# Nucleo_Shield.net
KiCad netlist of a schematic drawn in Altium Designer
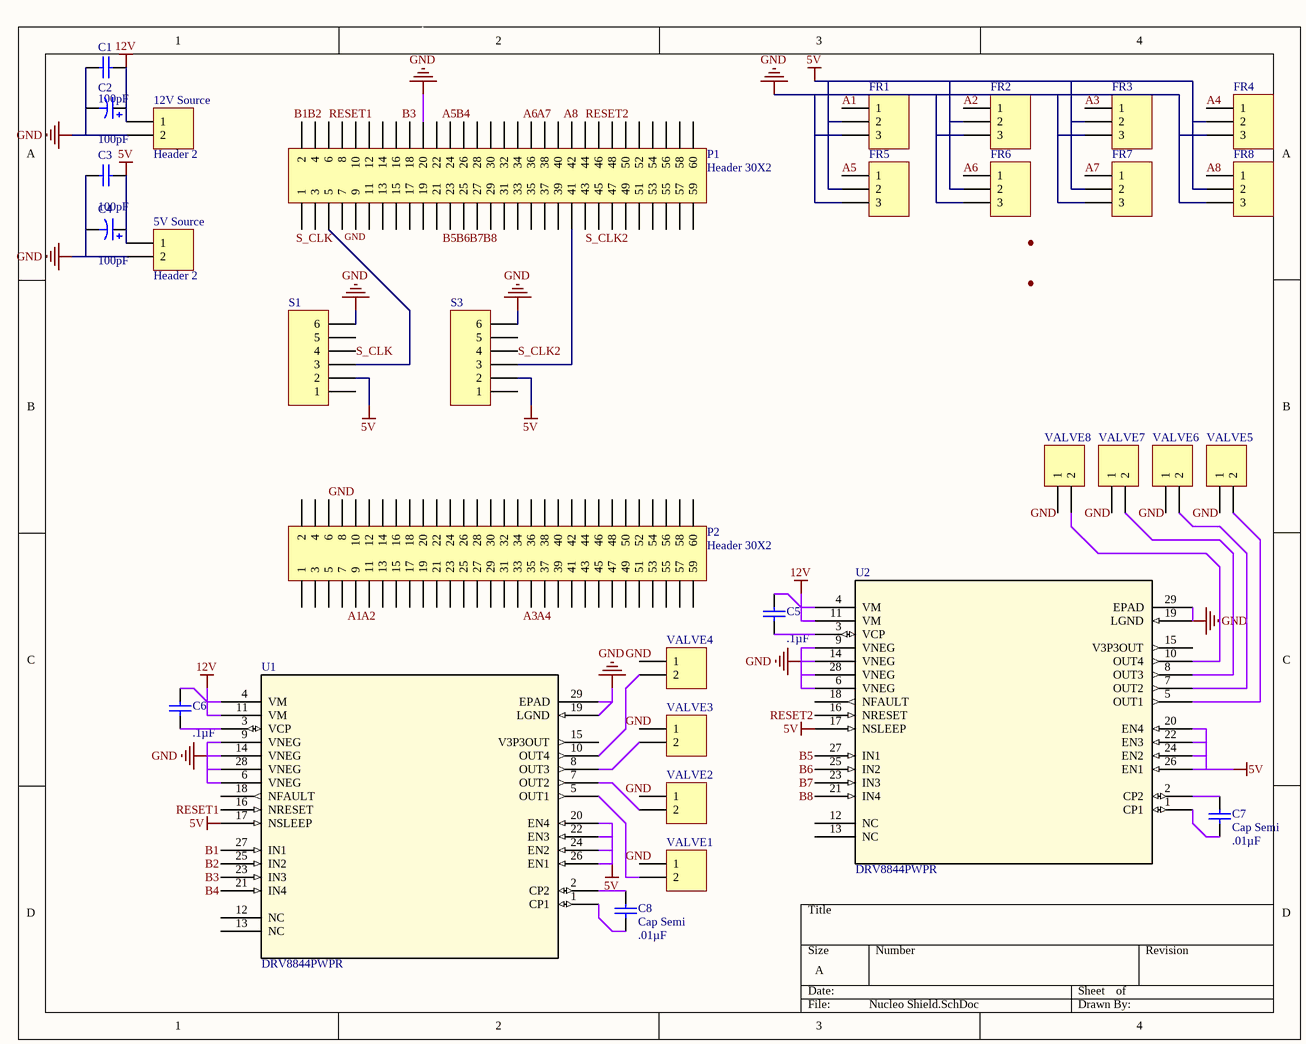
[diagram p0: Nucleo Shield.SchDoc]

(export (version "E")
  (design (tool "Eeschema 10.0.6"))
  (components
    (comp (ref "5V Source")
      (value "Header 2")
      (footprint "HDR1X2")
      (description "Header, 2-Pin")
      (fields (field (name "PUBLISHER") "Altium Limited"))
      (libsource (lib "Miscellaneous Connectors") (part "Header 2"))
    )
    (comp (ref "12V Source")
      (value "Header 2")
      (footprint "HDR1X2")
      (description "Header, 2-Pin")
      (fields (field (name "PUBLISHER") "Altium Limited"))
      (libsource (lib "Miscellaneous Connectors") (part "Header 2"))
    )
    (comp (ref "C1")
      (value "100pF")
      (footprint "C1206")
      (description "Capacitor (Semiconductor SIM Model)")
      (fields (field (name "Comment") "Cap Semi") (field (name "PUBLISHER") "Altium Limited"))
      (libsource (lib "Miscellaneous Devices") (part "Cap Semi"))
    )
    (comp (ref "C2")
      (value "100pF")
      (footprint "C0805")
      (description "Polarized Capacitor (Surface Mount)")
      (fields (field (name "Comment") "Cap Pol3") (field (name "PUBLISHER") "Altium Limited"))
      (libsource (lib "Miscellaneous Devices") (part "Cap Pol3"))
    )
    (comp (ref "C3")
      (value "100pF")
      (footprint "C1206")
      (description "Capacitor (Semiconductor SIM Model)")
      (fields (field (name "Comment") "Cap Semi") (field (name "PUBLISHER") "Altium Limited"))
      (libsource (lib "Miscellaneous Devices") (part "Cap Semi"))
    )
    (comp (ref "C4")
      (value "100pF")
      (footprint "C0805")
      (description "Polarized Capacitor (Surface Mount)")
      (fields (field (name "Comment") "Cap Pol3") (field (name "PUBLISHER") "Altium Limited"))
      (libsource (lib "Miscellaneous Devices") (part "Cap Pol3"))
    )
    (comp (ref "C5")
      (value ".1µF")
      (footprint "C1206")
      (description "Capacitor (Semiconductor SIM Model)")
      (fields (field (name "Comment") "Cap Semi") (field (name "PUBLISHER") "Altium Limited"))
      (libsource (lib "Miscellaneous Devices") (part "Cap Semi"))
    )
    (comp (ref "C6")
      (value ".1µF")
      (footprint "C1206")
      (description "Capacitor (Semiconductor SIM Model)")
      (fields (field (name "Comment") "Cap Semi") (field (name "PUBLISHER") "Altium Limited"))
      (libsource (lib "Miscellaneous Devices") (part "Cap Semi"))
    )
    (comp (ref "C7")
      (value "Cap Semi")
      (footprint "C1206")
      (description "Capacitor (Semiconductor SIM Model)")
      (fields (field (name "ALTIUM_VALUE") ".01µF") (field (name "PUBLISHER") "Altium Limited"))
      (libsource (lib "Miscellaneous Devices") (part "Cap Semi"))
    )
    (comp (ref "C8")
      (value "Cap Semi")
      (footprint "C1206")
      (description "Capacitor (Semiconductor SIM Model)")
      (fields (field (name "ALTIUM_VALUE") ".01µF") (field (name "PUBLISHER") "Altium Limited"))
      (libsource (lib "Miscellaneous Devices") (part "Cap Semi"))
    )
    (comp (ref "FR1")
      (value "FlowRate Sense")
      (footprint "HDR1X3")
      (description "Header, 3-Pin")
      (fields (field (name "PUBLISHER") "Altium Limited"))
      (libsource (lib "Miscellaneous Connectors") (part "Header 3"))
    )
    (comp (ref "FR2")
      (value "FlowRate Sense")
      (footprint "HDR1X3")
      (description "Header, 3-Pin")
      (fields (field (name "PUBLISHER") "Altium Limited"))
      (libsource (lib "Miscellaneous Connectors") (part "Header 3"))
    )
    (comp (ref "FR3")
      (value "FlowRate Sense")
      (footprint "HDR1X3")
      (description "Header, 3-Pin")
      (fields (field (name "PUBLISHER") "Altium Limited"))
      (libsource (lib "Miscellaneous Connectors") (part "Header 3"))
    )
    (comp (ref "FR4")
      (value "FlowRate Sense")
      (footprint "HDR1X3")
      (description "Header, 3-Pin")
      (fields (field (name "PUBLISHER") "Altium Limited"))
      (libsource (lib "Miscellaneous Connectors") (part "Header 3"))
    )
    (comp (ref "FR5")
      (value "FlowRate Sense")
      (footprint "HDR1X3")
      (description "Header, 3-Pin")
      (fields (field (name "PUBLISHER") "Altium Limited"))
      (libsource (lib "Miscellaneous Connectors") (part "Header 3"))
    )
    (comp (ref "FR6")
      (value "FlowRate Sense")
      (footprint "HDR1X3")
      (description "Header, 3-Pin")
      (fields (field (name "PUBLISHER") "Altium Limited"))
      (libsource (lib "Miscellaneous Connectors") (part "Header 3"))
    )
    (comp (ref "FR7")
      (value "FlowRate Sense")
      (footprint "HDR1X3")
      (description "Header, 3-Pin")
      (fields (field (name "PUBLISHER") "Altium Limited"))
      (libsource (lib "Miscellaneous Connectors") (part "Header 3"))
    )
    (comp (ref "FR8")
      (value "FlowRate Sense")
      (footprint "HDR1X3")
      (description "Header, 3-Pin")
      (fields (field (name "PUBLISHER") "Altium Limited"))
      (libsource (lib "Miscellaneous Connectors") (part "Header 3"))
    )
    (comp (ref "P1")
      (value "Header 30X2")
      (footprint "HDR2X30")
      (description "Header, 30-Pin, Dual row")
      (fields (field (name "PUBLISHER") "Altium Limited"))
      (libsource (lib "Miscellaneous Connectors") (part "Header 30X2"))
    )
    (comp (ref "P2")
      (value "Header 30X2")
      (footprint "HDR2X30")
      (description "Header, 30-Pin, Dual row")
      (fields (field (name "PUBLISHER") "Altium Limited"))
      (libsource (lib "Miscellaneous Connectors") (part "Header 30X2"))
    )
    (comp (ref "S1")
      (value "Header 6")
      (footprint "HDR1X6")
      (description "Header, 6-Pin")
      (fields (field (name "PUBLISHER") "Altium Limited"))
      (libsource (lib "Miscellaneous Connectors") (part "Header 6"))
    )
    (comp (ref "S3")
      (value "Header 6")
      (footprint "HDR1X6")
      (description "Header, 6-Pin")
      (fields (field (name "PUBLISHER") "Altium Limited"))
      (libsource (lib "Miscellaneous Connectors") (part "Header 6"))
    )
    (comp (ref "U1")
      (value "DRV8844PWPR")
      (footprint "PWP28_5P18X3P1")
      (description "Imported")
      (libsource (lib "AltiumDesigner") (part "DRV8844PWPR"))
    )
    (comp (ref "U2")
      (value "DRV8844PWPR")
      (footprint "PWP28_5P18X3P1")
      (description "Imported")
      (libsource (lib "AltiumDesigner") (part "DRV8844PWPR"))
    )
    (comp (ref "VALVE1")
      (value "Header 2")
      (footprint "HDR1X2")
      (description "Header, 2-Pin")
      (fields (field (name "PUBLISHER") "Altium Limited"))
      (libsource (lib "Miscellaneous Connectors") (part "Header 2"))
    )
    (comp (ref "VALVE2")
      (value "Header 2")
      (footprint "HDR1X2")
      (description "Header, 2-Pin")
      (fields (field (name "PUBLISHER") "Altium Limited"))
      (libsource (lib "Miscellaneous Connectors") (part "Header 2"))
    )
    (comp (ref "VALVE3")
      (value "Header 2")
      (footprint "HDR1X2")
      (description "Header, 2-Pin")
      (fields (field (name "PUBLISHER") "Altium Limited"))
      (libsource (lib "Miscellaneous Connectors") (part "Header 2"))
    )
    (comp (ref "VALVE4")
      (value "Header 2")
      (footprint "HDR1X2")
      (description "Header, 2-Pin")
      (fields (field (name "PUBLISHER") "Altium Limited"))
      (libsource (lib "Miscellaneous Connectors") (part "Header 2"))
    )
    (comp (ref "VALVE5")
      (value "Header 2")
      (footprint "HDR1X2")
      (description "Header, 2-Pin")
      (fields (field (name "PUBLISHER") "Altium Limited"))
      (libsource (lib "") (part "Header 2_1"))
    )
    (comp (ref "VALVE6")
      (value "Header 2")
      (footprint "HDR1X2")
      (description "Header, 2-Pin")
      (fields (field (name "PUBLISHER") "Altium Limited"))
      (libsource (lib "") (part "Header 2_1"))
    )
    (comp (ref "VALVE7")
      (value "Header 2")
      (footprint "HDR1X2")
      (description "Header, 2-Pin")
      (fields (field (name "PUBLISHER") "Altium Limited"))
      (libsource (lib "") (part "Header 2_1"))
    )
    (comp (ref "VALVE8")
      (value "Header 2")
      (footprint "HDR1X2")
      (description "Header, 2-Pin")
      (fields (field (name "PUBLISHER") "Altium Limited"))
      (libsource (lib "") (part "Header 2_1"))
    )
  )
  (nets
    (net (code "1") (name "/A1") (class "Default")
      (node (ref "FR1") (pin "1") (pinfunction "1_1") (pintype "passive"))
      (node (ref "P2") (pin "9") (pinfunction "9_9") (pintype "passive"))
    )
    (net (code "2") (name "/A2") (class "Default")
      (node (ref "FR2") (pin "1") (pinfunction "1_1") (pintype "passive"))
      (node (ref "P2") (pin "11") (pinfunction "11_11") (pintype "passive"))
    )
    (net (code "3") (name "/A3") (class "Default")
      (node (ref "FR3") (pin "1") (pinfunction "1_1") (pintype "passive"))
      (node (ref "P2") (pin "35") (pinfunction "35_35") (pintype "passive"))
    )
    (net (code "4") (name "/A4") (class "Default")
      (node (ref "FR4") (pin "1") (pinfunction "1_1") (pintype "passive"))
      (node (ref "P2") (pin "37") (pinfunction "37_37") (pintype "passive"))
    )
    (net (code "5") (name "/A5") (class "Default")
      (node (ref "FR5") (pin "1") (pinfunction "1_1") (pintype "passive"))
      (node (ref "P1") (pin "24") (pinfunction "24_24") (pintype "passive"))
    )
    (net (code "6") (name "/A6") (class "Default")
      (node (ref "FR6") (pin "1") (pinfunction "1_1") (pintype "passive"))
      (node (ref "P1") (pin "36") (pinfunction "36_36") (pintype "passive"))
    )
    (net (code "7") (name "/A7") (class "Default")
      (node (ref "FR7") (pin "1") (pinfunction "1_1") (pintype "passive"))
      (node (ref "P1") (pin "38") (pinfunction "38_38") (pintype "passive"))
    )
    (net (code "8") (name "/A8") (class "Default")
      (node (ref "FR8") (pin "1") (pinfunction "1_1") (pintype "passive"))
      (node (ref "P1") (pin "42") (pinfunction "42_42") (pintype "passive"))
    )
    (net (code "9") (name "/B1") (class "Default")
      (node (ref "P1") (pin "2") (pinfunction "2_2") (pintype "passive"))
      (node (ref "U1") (pin "27") (pinfunction "IN1_27") (pintype "input"))
    )
    (net (code "10") (name "/B2") (class "Default")
      (node (ref "P1") (pin "4") (pinfunction "4_4") (pintype "passive"))
      (node (ref "U1") (pin "25") (pinfunction "IN2_25") (pintype "input"))
    )
    (net (code "11") (name "/B3") (class "Default")
      (node (ref "P1") (pin "18") (pinfunction "18_18") (pintype "passive"))
      (node (ref "U1") (pin "23") (pinfunction "IN3_23") (pintype "input"))
    )
    (net (code "12") (name "/B4") (class "Default")
      (node (ref "P1") (pin "26") (pinfunction "26_26") (pintype "passive"))
      (node (ref "U1") (pin "21") (pinfunction "IN4_21") (pintype "input"))
    )
    (net (code "13") (name "/B5") (class "Default")
      (node (ref "P1") (pin "23") (pinfunction "23_23") (pintype "passive"))
      (node (ref "U2") (pin "27") (pinfunction "IN1_27") (pintype "input"))
    )
    (net (code "14") (name "/B6") (class "Default")
      (node (ref "P1") (pin "25") (pinfunction "25_25") (pintype "passive"))
      (node (ref "U2") (pin "25") (pinfunction "IN2_25") (pintype "input"))
    )
    (net (code "15") (name "/B7") (class "Default")
      (node (ref "P1") (pin "27") (pinfunction "27_27") (pintype "passive"))
      (node (ref "U2") (pin "23") (pinfunction "IN3_23") (pintype "input"))
    )
    (net (code "16") (name "/B8") (class "Default")
      (node (ref "P1") (pin "29") (pinfunction "29_29") (pintype "passive"))
      (node (ref "U2") (pin "21") (pinfunction "IN4_21") (pintype "input"))
    )
    (net (code "17") (name "/RESET1") (class "Default")
      (node (ref "P1") (pin "6") (pinfunction "6_6") (pintype "passive"))
      (node (ref "U1") (pin "16") (pinfunction "NRESET_16") (pintype "input"))
    )
    (net (code "18") (name "/RESET2") (class "Default")
      (node (ref "P1") (pin "44") (pinfunction "44_44") (pintype "passive"))
      (node (ref "U2") (pin "16") (pinfunction "NRESET_16") (pintype "input"))
    )
    (net (code "19") (name "/S_CLK") (class "Default")
      (node (ref "P1") (pin "3") (pinfunction "3_3") (pintype "passive"))
      (node (ref "S1") (pin "4") (pinfunction "4_4") (pintype "passive"))
    )
    (net (code "20") (name "/S_CLK2") (class "Default")
      (node (ref "P1") (pin "43") (pinfunction "43_43") (pintype "passive"))
      (node (ref "S3") (pin "4") (pinfunction "4_4") (pintype "passive"))
    )
    (net (code "21") (name "5V") (class "Default")
      (node (ref "5V Source") (pin "1") (pinfunction "1_1") (pintype "passive"))
      (node (ref "C3") (pin "2") (pinfunction "2_2") (pintype "passive"))
      (node (ref "C4") (pin "1") (pinfunction "1_1") (pintype "passive"))
      (node (ref "FR1") (pin "2") (pinfunction "2_2") (pintype "passive"))
      (node (ref "FR2") (pin "2") (pinfunction "2_2") (pintype "passive"))
      (node (ref "FR3") (pin "2") (pinfunction "2_2") (pintype "passive"))
      (node (ref "FR4") (pin "2") (pinfunction "2_2") (pintype "passive"))
      (node (ref "FR5") (pin "2") (pinfunction "2_2") (pintype "passive"))
      (node (ref "FR6") (pin "2") (pinfunction "2_2") (pintype "passive"))
      (node (ref "FR7") (pin "2") (pinfunction "2_2") (pintype "passive"))
      (node (ref "FR8") (pin "2") (pinfunction "2_2") (pintype "passive"))
      (node (ref "S1") (pin "2") (pinfunction "2_2") (pintype "passive"))
      (node (ref "S3") (pin "2") (pinfunction "2_2") (pintype "passive"))
      (node (ref "U1") (pin "17") (pinfunction "NSLEEP_17") (pintype "input"))
      (node (ref "U1") (pin "20") (pinfunction "EN4_20") (pintype "input"))
      (node (ref "U1") (pin "22") (pinfunction "EN3_22") (pintype "input"))
      (node (ref "U1") (pin "24") (pinfunction "EN2_24") (pintype "input"))
      (node (ref "U1") (pin "26") (pinfunction "EN1_26") (pintype "input"))
      (node (ref "U2") (pin "17") (pinfunction "NSLEEP_17") (pintype "input"))
      (node (ref "U2") (pin "20") (pinfunction "EN4_20") (pintype "input"))
      (node (ref "U2") (pin "22") (pinfunction "EN3_22") (pintype "input"))
      (node (ref "U2") (pin "24") (pinfunction "EN2_24") (pintype "input"))
      (node (ref "U2") (pin "26") (pinfunction "EN1_26") (pintype "input"))
    )
    (net (code "22") (name "12V") (class "Default")
      (node (ref "12V Source") (pin "1") (pinfunction "1_1") (pintype "passive"))
      (node (ref "C1") (pin "2") (pinfunction "2_2") (pintype "passive"))
      (node (ref "C2") (pin "1") (pinfunction "1_1") (pintype "passive"))
      (node (ref "C5") (pin "2") (pinfunction "2_2") (pintype "passive"))
      (node (ref "C6") (pin "2") (pinfunction "2_2") (pintype "passive"))
      (node (ref "U1") (pin "11") (pinfunction "VM_11") (pintype "power_in"))
      (node (ref "U1") (pin "4") (pinfunction "VM_4") (pintype "power_in"))
      (node (ref "U2") (pin "11") (pinfunction "VM_11") (pintype "power_in"))
      (node (ref "U2") (pin "4") (pinfunction "VM_4") (pintype "power_in"))
    )
    (net (code "23") (name "GND") (class "Default")
      (node (ref "12V Source") (pin "2") (pinfunction "2_2") (pintype "passive"))
      (node (ref "5V Source") (pin "2") (pinfunction "2_2") (pintype "passive"))
      (node (ref "C1") (pin "1") (pinfunction "1_1") (pintype "passive"))
      (node (ref "C2") (pin "2") (pinfunction "2_2") (pintype "passive"))
      (node (ref "C3") (pin "1") (pinfunction "1_1") (pintype "passive"))
      (node (ref "C4") (pin "2") (pinfunction "2_2") (pintype "passive"))
      (node (ref "FR1") (pin "3") (pinfunction "3_3") (pintype "passive"))
      (node (ref "FR2") (pin "3") (pinfunction "3_3") (pintype "passive"))
      (node (ref "FR3") (pin "3") (pinfunction "3_3") (pintype "passive"))
      (node (ref "FR4") (pin "3") (pinfunction "3_3") (pintype "passive"))
      (node (ref "FR5") (pin "3") (pinfunction "3_3") (pintype "passive"))
      (node (ref "FR6") (pin "3") (pinfunction "3_3") (pintype "passive"))
      (node (ref "FR7") (pin "3") (pinfunction "3_3") (pintype "passive"))
      (node (ref "FR8") (pin "3") (pinfunction "3_3") (pintype "passive"))
      (node (ref "P1") (pin "20") (pinfunction "20_20") (pintype "passive"))
      (node (ref "P1") (pin "9") (pinfunction "9_9") (pintype "passive"))
      (node (ref "P2") (pin "8") (pinfunction "8_8") (pintype "passive"))
      (node (ref "S1") (pin "6") (pinfunction "6_6") (pintype "passive"))
      (node (ref "S3") (pin "6") (pinfunction "6_6") (pintype "passive"))
      (node (ref "U1") (pin "14") (pinfunction "VNEG_14") (pintype "power_in"))
      (node (ref "U1") (pin "19") (pinfunction "LGND_19") (pintype "input"))
      (node (ref "U1") (pin "28") (pinfunction "VNEG_28") (pintype "power_in"))
      (node (ref "U1") (pin "29") (pinfunction "EPAD_29") (pintype "passive"))
      (node (ref "U1") (pin "6") (pinfunction "VNEG_6") (pintype "power_in"))
      (node (ref "U1") (pin "9") (pinfunction "VNEG_9") (pintype "power_in"))
      (node (ref "U2") (pin "14") (pinfunction "VNEG_14") (pintype "power_in"))
      (node (ref "U2") (pin "19") (pinfunction "LGND_19") (pintype "input"))
      (node (ref "U2") (pin "28") (pinfunction "VNEG_28") (pintype "power_in"))
      (node (ref "U2") (pin "29") (pinfunction "EPAD_29") (pintype "passive"))
      (node (ref "U2") (pin "6") (pinfunction "VNEG_6") (pintype "power_in"))
      (node (ref "U2") (pin "9") (pinfunction "VNEG_9") (pintype "power_in"))
      (node (ref "VALVE1") (pin "1") (pinfunction "1_1") (pintype "passive"))
      (node (ref "VALVE2") (pin "1") (pinfunction "1_1") (pintype "passive"))
      (node (ref "VALVE3") (pin "1") (pinfunction "1_1") (pintype "passive"))
      (node (ref "VALVE4") (pin "1") (pinfunction "1_1") (pintype "passive"))
      (node (ref "VALVE5") (pin "1") (pinfunction "1_1") (pintype "passive"))
      (node (ref "VALVE6") (pin "1") (pinfunction "1_1") (pintype "passive"))
      (node (ref "VALVE7") (pin "1") (pinfunction "1_1") (pintype "passive"))
      (node (ref "VALVE8") (pin "1") (pinfunction "1_1") (pintype "passive"))
    )
    (net (code "24") (name "Net-(P1-Pad5)") (class "Default")
      (node (ref "P1") (pin "5") (pinfunction "5_5") (pintype "passive"))
      (node (ref "S1") (pin "3") (pinfunction "3_3") (pintype "passive"))
    )
    (net (code "25") (name "Net-(P1-Pad41)") (class "Default")
      (node (ref "P1") (pin "41") (pinfunction "41_41") (pintype "passive"))
      (node (ref "S3") (pin "3") (pinfunction "3_3") (pintype "passive"))
    )
    (net (code "26") (name "Net-(U1-CP1)") (class "Default")
      (node (ref "C8") (pin "1") (pinfunction "1_1") (pintype "passive"))
      (node (ref "U1") (pin "1") (pinfunction "CP1_1") (pintype "bidirectional"))
    )
    (net (code "27") (name "Net-(U1-CP2)") (class "Default")
      (node (ref "C8") (pin "2") (pinfunction "2_2") (pintype "passive"))
      (node (ref "U1") (pin "2") (pinfunction "CP2_2") (pintype "bidirectional"))
    )
    (net (code "28") (name "Net-(U1-OUT1)") (class "Default")
      (node (ref "U1") (pin "5") (pinfunction "OUT1_5") (pintype "output"))
      (node (ref "VALVE1") (pin "2") (pinfunction "2_2") (pintype "passive"))
    )
    (net (code "29") (name "Net-(U1-OUT2)") (class "Default")
      (node (ref "U1") (pin "7") (pinfunction "OUT2_7") (pintype "output"))
      (node (ref "VALVE2") (pin "2") (pinfunction "2_2") (pintype "passive"))
    )
    (net (code "30") (name "Net-(U1-OUT3)") (class "Default")
      (node (ref "U1") (pin "8") (pinfunction "OUT3_8") (pintype "output"))
      (node (ref "VALVE3") (pin "2") (pinfunction "2_2") (pintype "passive"))
    )
    (net (code "31") (name "Net-(U1-OUT4)") (class "Default")
      (node (ref "U1") (pin "10") (pinfunction "OUT4_10") (pintype "output"))
      (node (ref "VALVE4") (pin "2") (pinfunction "2_2") (pintype "passive"))
    )
    (net (code "32") (name "Net-(U1-VCP)") (class "Default")
      (node (ref "C6") (pin "1") (pinfunction "1_1") (pintype "passive"))
      (node (ref "U1") (pin "3") (pinfunction "VCP_3") (pintype "bidirectional"))
    )
    (net (code "33") (name "Net-(U2-CP1)") (class "Default")
      (node (ref "C7") (pin "1") (pinfunction "1_1") (pintype "passive"))
      (node (ref "U2") (pin "1") (pinfunction "CP1_1") (pintype "bidirectional"))
    )
    (net (code "34") (name "Net-(U2-CP2)") (class "Default")
      (node (ref "C7") (pin "2") (pinfunction "2_2") (pintype "passive"))
      (node (ref "U2") (pin "2") (pinfunction "CP2_2") (pintype "bidirectional"))
    )
    (net (code "35") (name "Net-(U2-OUT1)") (class "Default")
      (node (ref "U2") (pin "5") (pinfunction "OUT1_5") (pintype "output"))
      (node (ref "VALVE5") (pin "2") (pinfunction "2_2") (pintype "passive"))
    )
    (net (code "36") (name "Net-(U2-OUT2)") (class "Default")
      (node (ref "U2") (pin "7") (pinfunction "OUT2_7") (pintype "output"))
      (node (ref "VALVE6") (pin "2") (pinfunction "2_2") (pintype "passive"))
    )
    (net (code "37") (name "Net-(U2-OUT3)") (class "Default")
      (node (ref "U2") (pin "8") (pinfunction "OUT3_8") (pintype "output"))
      (node (ref "VALVE7") (pin "2") (pinfunction "2_2") (pintype "passive"))
    )
    (net (code "38") (name "Net-(U2-OUT4)") (class "Default")
      (node (ref "U2") (pin "10") (pinfunction "OUT4_10") (pintype "output"))
      (node (ref "VALVE8") (pin "2") (pinfunction "2_2") (pintype "passive"))
    )
    (net (code "39") (name "Net-(U2-VCP)") (class "Default")
      (node (ref "C5") (pin "1") (pinfunction "1_1") (pintype "passive"))
      (node (ref "U2") (pin "3") (pinfunction "VCP_3") (pintype "bidirectional"))
    )
    (net (code "40") (name "unconnected-(P1-Pad1)") (class "Default")
      (node (ref "P1") (pin "1") (pinfunction "1_1") (pintype "passive"))
    )
    (net (code "41") (name "unconnected-(P1-Pad7)") (class "Default")
      (node (ref "P1") (pin "7") (pinfunction "7_7") (pintype "passive"))
    )
    (net (code "42") (name "unconnected-(P1-Pad8)") (class "Default")
      (node (ref "P1") (pin "8") (pinfunction "8_8") (pintype "passive"))
    )
    (net (code "43") (name "unconnected-(P1-Pad10)") (class "Default")
      (node (ref "P1") (pin "10") (pinfunction "10_10") (pintype "passive"))
    )
    (net (code "44") (name "unconnected-(P1-Pad11)") (class "Default")
      (node (ref "P1") (pin "11") (pinfunction "11_11") (pintype "passive"))
    )
    (net (code "45") (name "unconnected-(P1-Pad12)") (class "Default")
      (node (ref "P1") (pin "12") (pinfunction "12_12") (pintype "passive"))
    )
    (net (code "46") (name "unconnected-(P1-Pad13)") (class "Default")
      (node (ref "P1") (pin "13") (pinfunction "13_13") (pintype "passive"))
    )
    (net (code "47") (name "unconnected-(P1-Pad14)") (class "Default")
      (node (ref "P1") (pin "14") (pinfunction "14_14") (pintype "passive"))
    )
    (net (code "48") (name "unconnected-(P1-Pad15)") (class "Default")
      (node (ref "P1") (pin "15") (pinfunction "15_15") (pintype "passive"))
    )
    (net (code "49") (name "unconnected-(P1-Pad16)") (class "Default")
      (node (ref "P1") (pin "16") (pinfunction "16_16") (pintype "passive"))
    )
    (net (code "50") (name "unconnected-(P1-Pad17)") (class "Default")
      (node (ref "P1") (pin "17") (pinfunction "17_17") (pintype "passive"))
    )
    (net (code "51") (name "unconnected-(P1-Pad19)") (class "Default")
      (node (ref "P1") (pin "19") (pinfunction "19_19") (pintype "passive"))
    )
    (net (code "52") (name "unconnected-(P1-Pad21)") (class "Default")
      (node (ref "P1") (pin "21") (pinfunction "21_21") (pintype "passive"))
    )
    (net (code "53") (name "unconnected-(P1-Pad22)") (class "Default")
      (node (ref "P1") (pin "22") (pinfunction "22_22") (pintype "passive"))
    )
    (net (code "54") (name "unconnected-(P1-Pad28)") (class "Default")
      (node (ref "P1") (pin "28") (pinfunction "28_28") (pintype "passive"))
    )
    (net (code "55") (name "unconnected-(P1-Pad30)") (class "Default")
      (node (ref "P1") (pin "30") (pinfunction "30_30") (pintype "passive"))
    )
    (net (code "56") (name "unconnected-(P1-Pad31)") (class "Default")
      (node (ref "P1") (pin "31") (pinfunction "31_31") (pintype "passive"))
    )
    (net (code "57") (name "unconnected-(P1-Pad32)") (class "Default")
      (node (ref "P1") (pin "32") (pinfunction "32_32") (pintype "passive"))
    )
    (net (code "58") (name "unconnected-(P1-Pad33)") (class "Default")
      (node (ref "P1") (pin "33") (pinfunction "33_33") (pintype "passive"))
    )
    (net (code "59") (name "unconnected-(P1-Pad34)") (class "Default")
      (node (ref "P1") (pin "34") (pinfunction "34_34") (pintype "passive"))
    )
    (net (code "60") (name "unconnected-(P1-Pad35)") (class "Default")
      (node (ref "P1") (pin "35") (pinfunction "35_35") (pintype "passive"))
    )
    (net (code "61") (name "unconnected-(P1-Pad37)") (class "Default")
      (node (ref "P1") (pin "37") (pinfunction "37_37") (pintype "passive"))
    )
    (net (code "62") (name "unconnected-(P1-Pad39)") (class "Default")
      (node (ref "P1") (pin "39") (pinfunction "39_39") (pintype "passive"))
    )
    (net (code "63") (name "unconnected-(P1-Pad40)") (class "Default")
      (node (ref "P1") (pin "40") (pinfunction "40_40") (pintype "passive"))
    )
    (net (code "64") (name "unconnected-(P1-Pad45)") (class "Default")
      (node (ref "P1") (pin "45") (pinfunction "45_45") (pintype "passive"))
    )
    (net (code "65") (name "unconnected-(P1-Pad46)") (class "Default")
      (node (ref "P1") (pin "46") (pinfunction "46_46") (pintype "passive"))
    )
    (net (code "66") (name "unconnected-(P1-Pad47)") (class "Default")
      (node (ref "P1") (pin "47") (pinfunction "47_47") (pintype "passive"))
    )
    (net (code "67") (name "unconnected-(P1-Pad48)") (class "Default")
      (node (ref "P1") (pin "48") (pinfunction "48_48") (pintype "passive"))
    )
    (net (code "68") (name "unconnected-(P1-Pad49)") (class "Default")
      (node (ref "P1") (pin "49") (pinfunction "49_49") (pintype "passive"))
    )
    (net (code "69") (name "unconnected-(P1-Pad50)") (class "Default")
      (node (ref "P1") (pin "50") (pinfunction "50_50") (pintype "passive"))
    )
    (net (code "70") (name "unconnected-(P1-Pad51)") (class "Default")
      (node (ref "P1") (pin "51") (pinfunction "51_51") (pintype "passive"))
    )
    (net (code "71") (name "unconnected-(P1-Pad52)") (class "Default")
      (node (ref "P1") (pin "52") (pinfunction "52_52") (pintype "passive"))
    )
    (net (code "72") (name "unconnected-(P1-Pad53)") (class "Default")
      (node (ref "P1") (pin "53") (pinfunction "53_53") (pintype "passive"))
    )
    (net (code "73") (name "unconnected-(P1-Pad54)") (class "Default")
      (node (ref "P1") (pin "54") (pinfunction "54_54") (pintype "passive"))
    )
    (net (code "74") (name "unconnected-(P1-Pad55)") (class "Default")
      (node (ref "P1") (pin "55") (pinfunction "55_55") (pintype "passive"))
    )
    (net (code "75") (name "unconnected-(P1-Pad56)") (class "Default")
      (node (ref "P1") (pin "56") (pinfunction "56_56") (pintype "passive"))
    )
    (net (code "76") (name "unconnected-(P1-Pad57)") (class "Default")
      (node (ref "P1") (pin "57") (pinfunction "57_57") (pintype "passive"))
    )
    (net (code "77") (name "unconnected-(P1-Pad58)") (class "Default")
      (node (ref "P1") (pin "58") (pinfunction "58_58") (pintype "passive"))
    )
    (net (code "78") (name "unconnected-(P1-Pad59)") (class "Default")
      (node (ref "P1") (pin "59") (pinfunction "59_59") (pintype "passive"))
    )
    (net (code "79") (name "unconnected-(P1-Pad60)") (class "Default")
      (node (ref "P1") (pin "60") (pinfunction "60_60") (pintype "passive"))
    )
    (net (code "80") (name "unconnected-(P2-Pad1)") (class "Default")
      (node (ref "P2") (pin "1") (pinfunction "1_1") (pintype "passive"))
    )
    (net (code "81") (name "unconnected-(P2-Pad2)") (class "Default")
      (node (ref "P2") (pin "2") (pinfunction "2_2") (pintype "passive"))
    )
    (net (code "82") (name "unconnected-(P2-Pad3)") (class "Default")
      (node (ref "P2") (pin "3") (pinfunction "3_3") (pintype "passive"))
    )
    (net (code "83") (name "unconnected-(P2-Pad4)") (class "Default")
      (node (ref "P2") (pin "4") (pinfunction "4_4") (pintype "passive"))
    )
    (net (code "84") (name "unconnected-(P2-Pad5)") (class "Default")
      (node (ref "P2") (pin "5") (pinfunction "5_5") (pintype "passive"))
    )
    (net (code "85") (name "unconnected-(P2-Pad6)") (class "Default")
      (node (ref "P2") (pin "6") (pinfunction "6_6") (pintype "passive"))
    )
    (net (code "86") (name "unconnected-(P2-Pad7)") (class "Default")
      (node (ref "P2") (pin "7") (pinfunction "7_7") (pintype "passive"))
    )
    (net (code "87") (name "unconnected-(P2-Pad10)") (class "Default")
      (node (ref "P2") (pin "10") (pinfunction "10_10") (pintype "passive"))
    )
    (net (code "88") (name "unconnected-(P2-Pad12)") (class "Default")
      (node (ref "P2") (pin "12") (pinfunction "12_12") (pintype "passive"))
    )
    (net (code "89") (name "unconnected-(P2-Pad13)") (class "Default")
      (node (ref "P2") (pin "13") (pinfunction "13_13") (pintype "passive"))
    )
    (net (code "90") (name "unconnected-(P2-Pad14)") (class "Default")
      (node (ref "P2") (pin "14") (pinfunction "14_14") (pintype "passive"))
    )
    (net (code "91") (name "unconnected-(P2-Pad15)") (class "Default")
      (node (ref "P2") (pin "15") (pinfunction "15_15") (pintype "passive"))
    )
    (net (code "92") (name "unconnected-(P2-Pad16)") (class "Default")
      (node (ref "P2") (pin "16") (pinfunction "16_16") (pintype "passive"))
    )
    (net (code "93") (name "unconnected-(P2-Pad17)") (class "Default")
      (node (ref "P2") (pin "17") (pinfunction "17_17") (pintype "passive"))
    )
    (net (code "94") (name "unconnected-(P2-Pad18)") (class "Default")
      (node (ref "P2") (pin "18") (pinfunction "18_18") (pintype "passive"))
    )
    (net (code "95") (name "unconnected-(P2-Pad19)") (class "Default")
      (node (ref "P2") (pin "19") (pinfunction "19_19") (pintype "passive"))
    )
    (net (code "96") (name "unconnected-(P2-Pad20)") (class "Default")
      (node (ref "P2") (pin "20") (pinfunction "20_20") (pintype "passive"))
    )
    (net (code "97") (name "unconnected-(P2-Pad21)") (class "Default")
      (node (ref "P2") (pin "21") (pinfunction "21_21") (pintype "passive"))
    )
    (net (code "98") (name "unconnected-(P2-Pad22)") (class "Default")
      (node (ref "P2") (pin "22") (pinfunction "22_22") (pintype "passive"))
    )
    (net (code "99") (name "unconnected-(P2-Pad23)") (class "Default")
      (node (ref "P2") (pin "23") (pinfunction "23_23") (pintype "passive"))
    )
    (net (code "100") (name "unconnected-(P2-Pad24)") (class "Default")
      (node (ref "P2") (pin "24") (pinfunction "24_24") (pintype "passive"))
    )
    (net (code "101") (name "unconnected-(P2-Pad25)") (class "Default")
      (node (ref "P2") (pin "25") (pinfunction "25_25") (pintype "passive"))
    )
    (net (code "102") (name "unconnected-(P2-Pad26)") (class "Default")
      (node (ref "P2") (pin "26") (pinfunction "26_26") (pintype "passive"))
    )
    (net (code "103") (name "unconnected-(P2-Pad27)") (class "Default")
      (node (ref "P2") (pin "27") (pinfunction "27_27") (pintype "passive"))
    )
    (net (code "104") (name "unconnected-(P2-Pad28)") (class "Default")
      (node (ref "P2") (pin "28") (pinfunction "28_28") (pintype "passive"))
    )
    (net (code "105") (name "unconnected-(P2-Pad29)") (class "Default")
      (node (ref "P2") (pin "29") (pinfunction "29_29") (pintype "passive"))
    )
    (net (code "106") (name "unconnected-(P2-Pad30)") (class "Default")
      (node (ref "P2") (pin "30") (pinfunction "30_30") (pintype "passive"))
    )
    (net (code "107") (name "unconnected-(P2-Pad31)") (class "Default")
      (node (ref "P2") (pin "31") (pinfunction "31_31") (pintype "passive"))
    )
    (net (code "108") (name "unconnected-(P2-Pad32)") (class "Default")
      (node (ref "P2") (pin "32") (pinfunction "32_32") (pintype "passive"))
    )
    (net (code "109") (name "unconnected-(P2-Pad33)") (class "Default")
      (node (ref "P2") (pin "33") (pinfunction "33_33") (pintype "passive"))
    )
    (net (code "110") (name "unconnected-(P2-Pad34)") (class "Default")
      (node (ref "P2") (pin "34") (pinfunction "34_34") (pintype "passive"))
    )
    (net (code "111") (name "unconnected-(P2-Pad36)") (class "Default")
      (node (ref "P2") (pin "36") (pinfunction "36_36") (pintype "passive"))
    )
    (net (code "112") (name "unconnected-(P2-Pad38)") (class "Default")
      (node (ref "P2") (pin "38") (pinfunction "38_38") (pintype "passive"))
    )
    (net (code "113") (name "unconnected-(P2-Pad39)") (class "Default")
      (node (ref "P2") (pin "39") (pinfunction "39_39") (pintype "passive"))
    )
    (net (code "114") (name "unconnected-(P2-Pad40)") (class "Default")
      (node (ref "P2") (pin "40") (pinfunction "40_40") (pintype "passive"))
    )
    (net (code "115") (name "unconnected-(P2-Pad41)") (class "Default")
      (node (ref "P2") (pin "41") (pinfunction "41_41") (pintype "passive"))
    )
    (net (code "116") (name "unconnected-(P2-Pad42)") (class "Default")
      (node (ref "P2") (pin "42") (pinfunction "42_42") (pintype "passive"))
    )
    (net (code "117") (name "unconnected-(P2-Pad43)") (class "Default")
      (node (ref "P2") (pin "43") (pinfunction "43_43") (pintype "passive"))
    )
    (net (code "118") (name "unconnected-(P2-Pad44)") (class "Default")
      (node (ref "P2") (pin "44") (pinfunction "44_44") (pintype "passive"))
    )
    (net (code "119") (name "unconnected-(P2-Pad45)") (class "Default")
      (node (ref "P2") (pin "45") (pinfunction "45_45") (pintype "passive"))
    )
    (net (code "120") (name "unconnected-(P2-Pad46)") (class "Default")
      (node (ref "P2") (pin "46") (pinfunction "46_46") (pintype "passive"))
    )
    (net (code "121") (name "unconnected-(P2-Pad47)") (class "Default")
      (node (ref "P2") (pin "47") (pinfunction "47_47") (pintype "passive"))
    )
    (net (code "122") (name "unconnected-(P2-Pad48)") (class "Default")
      (node (ref "P2") (pin "48") (pinfunction "48_48") (pintype "passive"))
    )
    (net (code "123") (name "unconnected-(P2-Pad49)") (class "Default")
      (node (ref "P2") (pin "49") (pinfunction "49_49") (pintype "passive"))
    )
    (net (code "124") (name "unconnected-(P2-Pad50)") (class "Default")
      (node (ref "P2") (pin "50") (pinfunction "50_50") (pintype "passive"))
    )
    (net (code "125") (name "unconnected-(P2-Pad51)") (class "Default")
      (node (ref "P2") (pin "51") (pinfunction "51_51") (pintype "passive"))
    )
    (net (code "126") (name "unconnected-(P2-Pad52)") (class "Default")
      (node (ref "P2") (pin "52") (pinfunction "52_52") (pintype "passive"))
    )
    (net (code "127") (name "unconnected-(P2-Pad53)") (class "Default")
      (node (ref "P2") (pin "53") (pinfunction "53_53") (pintype "passive"))
    )
    (net (code "128") (name "unconnected-(P2-Pad54)") (class "Default")
      (node (ref "P2") (pin "54") (pinfunction "54_54") (pintype "passive"))
    )
    (net (code "129") (name "unconnected-(P2-Pad55)") (class "Default")
      (node (ref "P2") (pin "55") (pinfunction "55_55") (pintype "passive"))
    )
    (net (code "130") (name "unconnected-(P2-Pad56)") (class "Default")
      (node (ref "P2") (pin "56") (pinfunction "56_56") (pintype "passive"))
    )
    (net (code "131") (name "unconnected-(P2-Pad57)") (class "Default")
      (node (ref "P2") (pin "57") (pinfunction "57_57") (pintype "passive"))
    )
    (net (code "132") (name "unconnected-(P2-Pad58)") (class "Default")
      (node (ref "P2") (pin "58") (pinfunction "58_58") (pintype "passive"))
    )
    (net (code "133") (name "unconnected-(P2-Pad59)") (class "Default")
      (node (ref "P2") (pin "59") (pinfunction "59_59") (pintype "passive"))
    )
    (net (code "134") (name "unconnected-(P2-Pad60)") (class "Default")
      (node (ref "P2") (pin "60") (pinfunction "60_60") (pintype "passive"))
    )
    (net (code "135") (name "unconnected-(S1-Pad1)") (class "Default")
      (node (ref "S1") (pin "1") (pinfunction "1_1") (pintype "passive"))
    )
    (net (code "136") (name "unconnected-(S1-Pad5)") (class "Default")
      (node (ref "S1") (pin "5") (pinfunction "5_5") (pintype "passive"))
    )
    (net (code "137") (name "unconnected-(S3-Pad1)") (class "Default")
      (node (ref "S3") (pin "1") (pinfunction "1_1") (pintype "passive"))
    )
    (net (code "138") (name "unconnected-(S3-Pad5)") (class "Default")
      (node (ref "S3") (pin "5") (pinfunction "5_5") (pintype "passive"))
    )
    (net (code "139") (name "unconnected-(U1-NC-Pad12)") (class "Default")
      (node (ref "U1") (pin "12") (pinfunction "NC_12") (pintype "passive"))
    )
    (net (code "140") (name "unconnected-(U1-NC-Pad13)") (class "Default")
      (node (ref "U1") (pin "13") (pinfunction "NC_13") (pintype "passive"))
    )
    (net (code "141") (name "unconnected-(U1-NFAULT-Pad18)") (class "Default")
      (node (ref "U1") (pin "18") (pinfunction "NFAULT_18") (pintype "output"))
    )
    (net (code "142") (name "unconnected-(U1-V3P3OUT-Pad15)") (class "Default")
      (node (ref "U1") (pin "15") (pinfunction "V3P3OUT_15") (pintype "output"))
    )
    (net (code "143") (name "unconnected-(U2-NC-Pad12)") (class "Default")
      (node (ref "U2") (pin "12") (pinfunction "NC_12") (pintype "passive"))
    )
    (net (code "144") (name "unconnected-(U2-NC-Pad13)") (class "Default")
      (node (ref "U2") (pin "13") (pinfunction "NC_13") (pintype "passive"))
    )
    (net (code "145") (name "unconnected-(U2-NFAULT-Pad18)") (class "Default")
      (node (ref "U2") (pin "18") (pinfunction "NFAULT_18") (pintype "output"))
    )
    (net (code "146") (name "unconnected-(U2-V3P3OUT-Pad15)") (class "Default")
      (node (ref "U2") (pin "15") (pinfunction "V3P3OUT_15") (pintype "output"))
    )
  )
)
